# Sheet1.net
KiCad netlist of a schematic drawn in Altium Designer
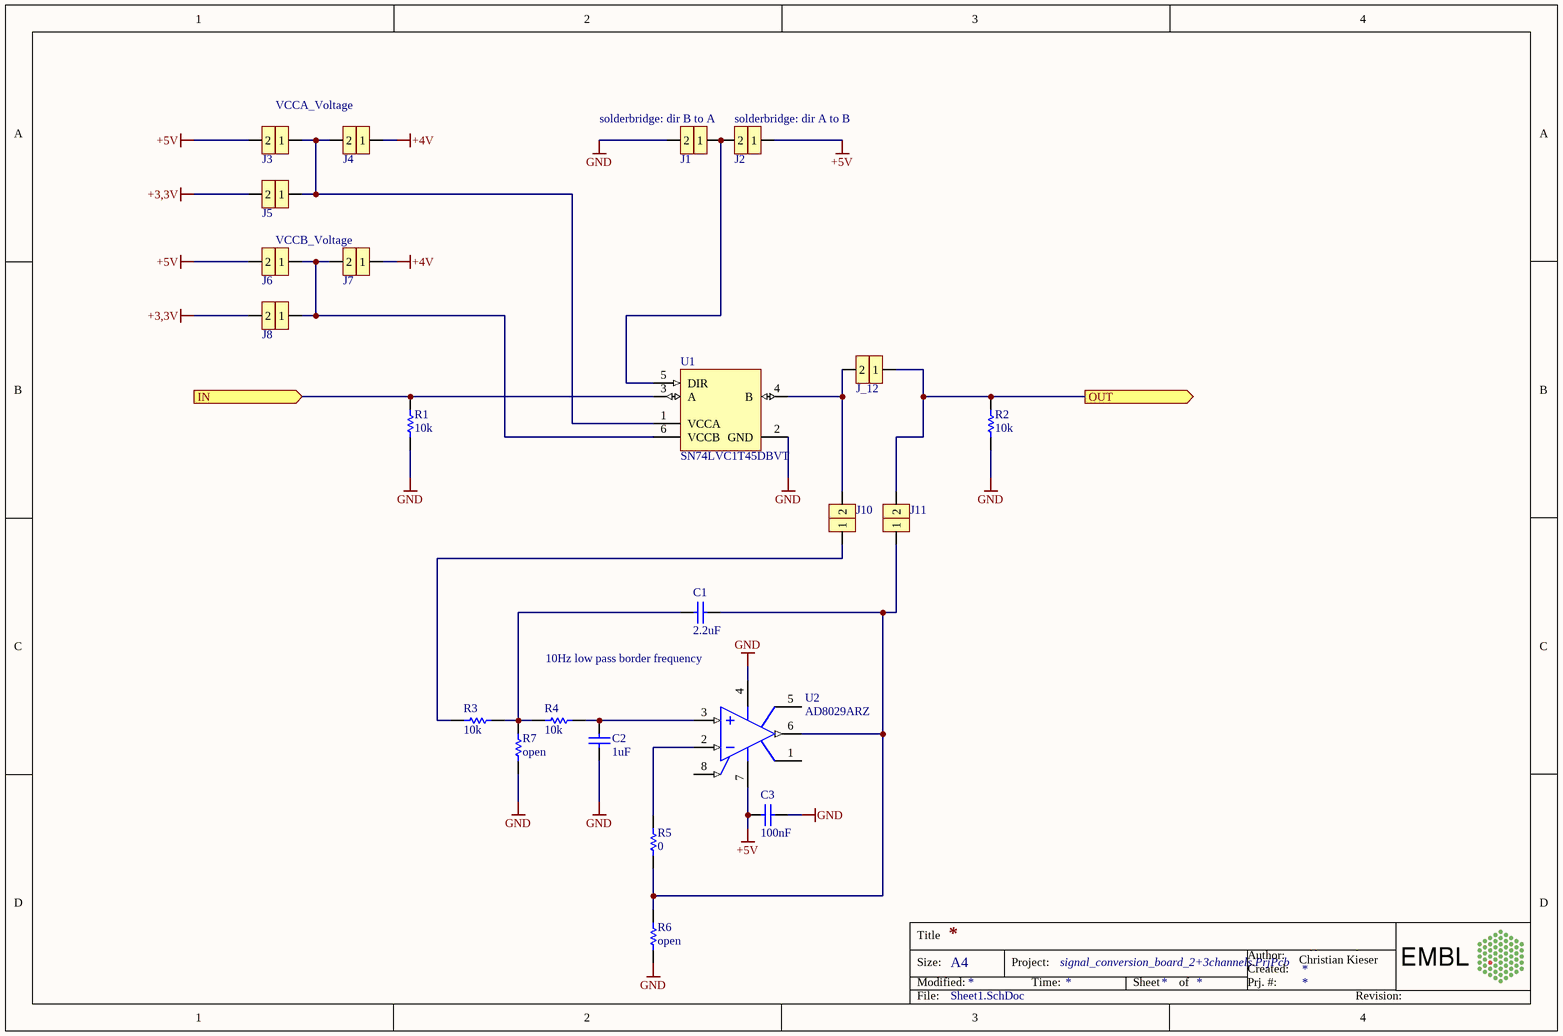
[diagram p0: Sheet1.SchDoc]

(export (version "E")
  (design (tool "Eeschema 10.0.6"))
  (components
    (comp (ref "C1")
      (value "2.2uF")
      (footprint "CAPC1206(3216)190_M")
      (description "CAP CER 2.2UF 10V X7R 1206")
      (fields (field (name "PARTNUMBER") "885012208015") (field (name "MANUFACTURER") "Wurth Electronics"))
      (libsource (lib "Altium Vault EMBL 3") (part "CMP-001-0162-A.1"))
    )
    (comp (ref "C2")
      (value "1uF")
      (footprint "CAPC1206(3216)190_N")
      (description "CAP CER 1UF 10V X7R 1206")
      (fields
        (field (name "MANUFACTURER") "Wurth Electronics Inc.")
        (field (name "MANUFACTURER PART NUMBER") "885012208013")
      )
      (libsource (lib "Altium Vault EMBL 3") (part "CMP-001-0138-A.2"))
    )
    (comp (ref "C3")
      (value "100nF")
      (footprint "CAPC2013X88X50ML20T25")
      (description "generic 0805 COG oder X7R Vielschichtkondensatoren max. +/-10%")
      (libsource (lib "Altium Vault EMBL") (part "CMP-001-0082-2"))
    )
    (comp (ref "J1")
      (value "normal solderbridge")
      (footprint "PCBComponent")
      (libsource (lib "") (part "CMP-001-0133-A.1_1"))
    )
    (comp (ref "J2")
      (value "normal solderbridge")
      (footprint "PCBComponent")
      (libsource (lib "") (part "CMP-001-0133-A.1_1"))
    )
    (comp (ref "J3")
      (value "normal solderbridge")
      (footprint "PCBComponent")
      (libsource (lib "") (part "CMP-001-0133-A.1_1"))
    )
    (comp (ref "J4")
      (value "normal solderbridge")
      (footprint "PCBComponent")
      (libsource (lib "") (part "CMP-001-0133-A.1_1"))
    )
    (comp (ref "J5")
      (value "normal solderbridge")
      (footprint "PCBComponent")
      (libsource (lib "") (part "CMP-001-0133-A.1_1"))
    )
    (comp (ref "J6")
      (value "normal solderbridge")
      (footprint "PCBComponent")
      (libsource (lib "") (part "CMP-001-0133-A.1_1"))
    )
    (comp (ref "J7")
      (value "normal solderbridge")
      (footprint "PCBComponent")
      (libsource (lib "") (part "CMP-001-0133-A.1_1"))
    )
    (comp (ref "J8")
      (value "normal solderbridge")
      (footprint "PCBComponent")
      (libsource (lib "") (part "CMP-001-0133-A.1_1"))
    )
    (comp (ref "J10")
      (value "normal solderbridge")
      (footprint "PCBComponent")
      (libsource (lib "Altium Vault EMBL") (part "CMP-001-0133-A.1"))
    )
    (comp (ref "J11")
      (value "normal solderbridge")
      (footprint "PCBComponent")
      (libsource (lib "Altium Vault EMBL") (part "CMP-001-0133-A.1"))
    )
    (comp (ref "J_12")
      (value "normal solderbridge")
      (footprint "PCBComponent")
      (libsource (lib "") (part "CMP-001-0133-A.1_1"))
    )
    (comp (ref "R1")
      (value "10k")
      (footprint "YAGO-RC0805_M")
      (description "0805 Yageo Standard BlackBox Resistors")
      (fields (field (name "TOLERANCE") "±1%") (field (name "MANUFACTURER") "Yageo"))
      (libsource (lib "Altium Vault EMBL") (part "CMP-001-0027-2"))
    )
    (comp (ref "R2")
      (value "10k")
      (footprint "YAGO-RC0805_M")
      (description "0805 Yageo Standard BlackBox Resistors")
      (fields (field (name "TOLERANCE") "±1%") (field (name "MANUFACTURER") "Yageo"))
      (libsource (lib "Altium Vault EMBL") (part "CMP-001-0027-2"))
    )
    (comp (ref "R3")
      (value "10k")
      (footprint "YAGO-RC0805_M")
      (description "0805 Yageo Standard BlackBox Resistors")
      (fields (field (name "TOLERANCE") "±1%") (field (name "MANUFACTURER") "Yageo"))
      (libsource (lib "Altium Vault EMBL") (part "CMP-001-0027-2"))
    )
    (comp (ref "R4")
      (value "10k")
      (footprint "YAGO-RC0805_M")
      (description "0805 Yageo Standard BlackBox Resistors")
      (fields (field (name "TOLERANCE") "±1%") (field (name "MANUFACTURER") "Yageo"))
      (libsource (lib "Altium Vault EMBL") (part "CMP-001-0027-2"))
    )
    (comp (ref "R5")
      (value "0")
      (footprint "YAGO-RC0805_M")
      (description "0805 Yageo Standard BlackBox Resistors")
      (fields (field (name "TOLERANCE") "±1%") (field (name "MANUFACTURER") "Yageo"))
      (libsource (lib "Altium Vault EMBL") (part "CMP-001-0027-2"))
    )
    (comp (ref "R6")
      (value "open")
      (footprint "YAGO-RC0805_M")
      (description "0805 Yageo Standard BlackBox Resistors")
      (fields (field (name "TOLERANCE") "±1%") (field (name "MANUFACTURER") "Yageo"))
      (libsource (lib "Altium Vault EMBL") (part "CMP-001-0027-2"))
    )
    (comp (ref "R7")
      (value "open")
      (footprint "YAGO-RC0805_M")
      (description "0805 Yageo Standard BlackBox Resistors")
      (fields (field (name "TOLERANCE") "±1%") (field (name "MANUFACTURER") "Yageo"))
      (libsource (lib "Altium Vault EMBL") (part "CMP-001-0027-2"))
    )
    (comp (ref "U1")
      (value "SN74LVC1T45DBVT")
      (footprint "DBV0006A_M")
      (fields
        (field (name "MANUFACTURER") "Texas Instruments")
        (field (name "GENERIC PART NUMBER") "SN74LVC1T45")
        (field (name "PARTNUMBER") "SN74LVC1T45DBVTG4")
      )
      (libsource (lib "Altium Vault EMBL 3") (part "TI-SN74XVC1T45-6"))
    )
    (comp (ref "U2")
      (value "AD8029ARZ")
      (footprint "ADI-R-8_L")
      (fields (field (name "MANUFACTURER") "Analog Devices") (field (name "GENERIC PART NUMBER") "AD8029"))
      (libsource (lib "Altium Vault EMBL") (part "CMP-00480-1"))
    )
  )
  (nets
    (net (code "1") (name "+3,3V") (class "Default")
      (node (ref "J5") (pin "2") (pinfunction "2_2") (pintype "passive"))
      (node (ref "J8") (pin "2") (pinfunction "2_2") (pintype "passive"))
    )
    (net (code "2") (name "+4V") (class "Default")
      (node (ref "J4") (pin "1") (pinfunction "1_1") (pintype "passive"))
      (node (ref "J7") (pin "1") (pinfunction "1_1") (pintype "passive"))
    )
    (net (code "3") (name "+5V") (class "Default")
      (node (ref "C3") (pin "2") (pinfunction "2_2") (pintype "passive"))
      (node (ref "J2") (pin "1") (pinfunction "1_1") (pintype "passive"))
      (node (ref "J3") (pin "2") (pinfunction "2_2") (pintype "passive"))
      (node (ref "J6") (pin "2") (pinfunction "2_2") (pintype "passive"))
      (node (ref "U2") (pin "7") (pinfunction "+VS_7") (pintype "power_in"))
    )
    (net (code "4") (name "/IN") (class "Default")
      (node (ref "R1") (pin "2") (pinfunction "2_2") (pintype "passive"))
      (node (ref "U1") (pin "3") (pinfunction "A_3") (pintype "bidirectional"))
    )
    (net (code "5") (name "/OUT") (class "Default")
      (node (ref "J11") (pin "2") (pinfunction "2_2") (pintype "passive"))
      (node (ref "J_12") (pin "1") (pinfunction "1_1") (pintype "passive"))
      (node (ref "R2") (pin "2") (pinfunction "2_2") (pintype "passive"))
    )
    (net (code "6") (name "GND") (class "Default")
      (node (ref "C2") (pin "1") (pinfunction "1_1") (pintype "passive"))
      (node (ref "C3") (pin "1") (pinfunction "1_1") (pintype "passive"))
      (node (ref "J1") (pin "2") (pinfunction "2_2") (pintype "passive"))
      (node (ref "R1") (pin "1") (pinfunction "1_1") (pintype "passive"))
      (node (ref "R2") (pin "1") (pinfunction "1_1") (pintype "passive"))
      (node (ref "R6") (pin "2") (pinfunction "2_2") (pintype "passive"))
      (node (ref "R7") (pin "2") (pinfunction "2_2") (pintype "passive"))
      (node (ref "U1") (pin "2") (pinfunction "GND_2") (pintype "power_in"))
      (node (ref "U2") (pin "4") (pinfunction "-VS_4") (pintype "power_in"))
    )
    (net (code "7") (name "Net-(C1-Pad1)") (class "Default")
      (node (ref "C1") (pin "1") (pinfunction "1_1") (pintype "passive"))
      (node (ref "R3") (pin "1") (pinfunction "1_1") (pintype "passive"))
      (node (ref "R4") (pin "2") (pinfunction "2_2") (pintype "passive"))
      (node (ref "R7") (pin "1") (pinfunction "1_1") (pintype "passive"))
    )
    (net (code "8") (name "Net-(J10-Pad1)") (class "Default")
      (node (ref "J10") (pin "1") (pinfunction "1_1") (pintype "passive"))
      (node (ref "R3") (pin "2") (pinfunction "2_2") (pintype "passive"))
    )
    (net (code "9") (name "Net-(U1-B)") (class "Default")
      (node (ref "J10") (pin "2") (pinfunction "2_2") (pintype "passive"))
      (node (ref "J_12") (pin "2") (pinfunction "2_2") (pintype "passive"))
      (node (ref "U1") (pin "4") (pinfunction "B_4") (pintype "bidirectional"))
    )
    (net (code "10") (name "Net-(U1-DIR)") (class "Default")
      (node (ref "J1") (pin "1") (pinfunction "1_1") (pintype "passive"))
      (node (ref "J2") (pin "2") (pinfunction "2_2") (pintype "passive"))
      (node (ref "U1") (pin "5") (pinfunction "DIR_5") (pintype "input"))
    )
    (net (code "11") (name "Net-(U1-VCCA)") (class "Default")
      (node (ref "J3") (pin "1") (pinfunction "1_1") (pintype "passive"))
      (node (ref "J4") (pin "2") (pinfunction "2_2") (pintype "passive"))
      (node (ref "J5") (pin "1") (pinfunction "1_1") (pintype "passive"))
      (node (ref "U1") (pin "1") (pinfunction "VCCA_1") (pintype "power_in"))
    )
    (net (code "12") (name "Net-(U1-VCCB)") (class "Default")
      (node (ref "J6") (pin "1") (pinfunction "1_1") (pintype "passive"))
      (node (ref "J7") (pin "2") (pinfunction "2_2") (pintype "passive"))
      (node (ref "J8") (pin "1") (pinfunction "1_1") (pintype "passive"))
      (node (ref "U1") (pin "6") (pinfunction "VCCB_6") (pintype "power_in"))
    )
    (net (code "13") (name "Net-(U2-+IN)") (class "Default")
      (node (ref "C2") (pin "2") (pinfunction "2_2") (pintype "passive"))
      (node (ref "R4") (pin "1") (pinfunction "1_1") (pintype "passive"))
      (node (ref "U2") (pin "3") (pinfunction "+IN_3") (pintype "input"))
    )
    (net (code "14") (name "Net-(U2--IN)") (class "Default")
      (node (ref "R5") (pin "1") (pinfunction "1_1") (pintype "passive"))
      (node (ref "U2") (pin "2") (pinfunction "-IN_2") (pintype "input"))
    )
    (net (code "15") (name "Net-(U2-VOUT)") (class "Default")
      (node (ref "C1") (pin "2") (pinfunction "2_2") (pintype "passive"))
      (node (ref "J11") (pin "1") (pinfunction "1_1") (pintype "passive"))
      (node (ref "R5") (pin "2") (pinfunction "2_2") (pintype "passive"))
      (node (ref "R6") (pin "1") (pinfunction "1_1") (pintype "passive"))
      (node (ref "U2") (pin "6") (pinfunction "VOUT_6") (pintype "output"))
    )
    (net (code "16") (name "unconnected-(U2-NC-Pad1)") (class "Default")
      (node (ref "U2") (pin "1") (pinfunction "NC_1") (pintype "passive"))
    )
    (net (code "17") (name "unconnected-(U2-NC-Pad5)") (class "Default")
      (node (ref "U2") (pin "5") (pinfunction "NC_5") (pintype "passive"))
    )
    (net (code "18") (name "unconnected-(U2-~{DISABLE}-Pad8)") (class "Default")
      (node (ref "U2") (pin "8") (pinfunction "~{DISABLE}_8") (pintype "input"))
    )
  )
)
